# OVMS-SimpleConsole.net
KiCad netlist of a schematic drawn in EAGLE
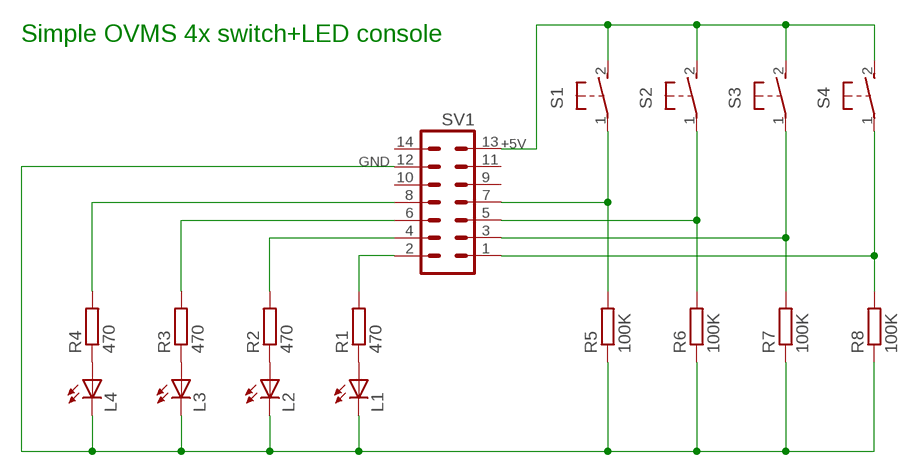
[diagram p0: schematic, sheet 1]

(export (version "E")
  (design (tool "Eeschema 10.0.6"))
  (components
    (comp (ref "L1")
      (value "LED5MM")
      (footprint "eagle-import:LED5MM")
      (libsource (lib "eagle-import") (part "LED5MM"))
    )
    (comp (ref "L2")
      (value "LED5MM")
      (footprint "eagle-import:LED5MM")
      (libsource (lib "eagle-import") (part "LED5MM"))
    )
    (comp (ref "L3")
      (value "LED5MM")
      (footprint "eagle-import:LED5MM")
      (libsource (lib "eagle-import") (part "LED5MM"))
    )
    (comp (ref "L4")
      (value "LED5MM")
      (footprint "eagle-import:LED5MM")
      (libsource (lib "eagle-import") (part "LED5MM"))
    )
    (comp (ref "R1")
      (value "470")
      (footprint "eagle-import:0204_7")
      (libsource (lib "eagle-import") (part "R-EU_0204/7"))
    )
    (comp (ref "R2")
      (value "470")
      (footprint "eagle-import:0204_7")
      (libsource (lib "eagle-import") (part "R-EU_0204/7"))
    )
    (comp (ref "R3")
      (value "470")
      (footprint "eagle-import:0204_7")
      (libsource (lib "eagle-import") (part "R-EU_0204/7"))
    )
    (comp (ref "R4")
      (value "470")
      (footprint "eagle-import:0204_7")
      (libsource (lib "eagle-import") (part "R-EU_0204/7"))
    )
    (comp (ref "R5")
      (value "100K")
      (footprint "eagle-import:0204_7")
      (libsource (lib "eagle-import") (part "R-EU_0204/7"))
    )
    (comp (ref "R6")
      (value "100K")
      (footprint "eagle-import:0204_7")
      (libsource (lib "eagle-import") (part "R-EU_0204/7"))
    )
    (comp (ref "R7")
      (value "100K")
      (footprint "eagle-import:0204_7")
      (libsource (lib "eagle-import") (part "R-EU_0204/7"))
    )
    (comp (ref "R8")
      (value "100K")
      (footprint "eagle-import:0204_7")
      (libsource (lib "eagle-import") (part "R-EU_0204/7"))
    )
    (comp (ref "S1")
      (value "31-XX")
      (footprint "eagle-import:B3F-31XX")
      (fields (field (name "MPN") "B3F-3100"))
      (libsource (lib "eagle-import") (part "31-XX"))
    )
    (comp (ref "S2")
      (value "31-XX")
      (footprint "eagle-import:B3F-31XX")
      (fields (field (name "MPN") "B3F-3100"))
      (libsource (lib "eagle-import") (part "31-XX"))
    )
    (comp (ref "S3")
      (value "31-XX")
      (footprint "eagle-import:B3F-31XX")
      (fields (field (name "MPN") "B3F-3100"))
      (libsource (lib "eagle-import") (part "31-XX"))
    )
    (comp (ref "S4")
      (value "31-XX")
      (footprint "eagle-import:B3F-31XX")
      (fields (field (name "MPN") "B3F-3100"))
      (libsource (lib "eagle-import") (part "31-XX"))
    )
    (comp (ref "SV1")
      (value "14P")
      (footprint "eagle-import:14P")
      (libsource (lib "eagle-import") (part "14P"))
    )
  )
  (nets
    (net (code "1") (name "/+5V") (class "Default")
      (node (ref "S1") (pin "2") (pinfunction "S_2") (pintype "passive"))
      (node (ref "S2") (pin "2") (pinfunction "S_2") (pintype "passive"))
      (node (ref "S3") (pin "2") (pinfunction "S_2") (pintype "passive"))
      (node (ref "S4") (pin "2") (pinfunction "S_2") (pintype "passive"))
      (node (ref "SV1") (pin "13") (pinfunction "13_13") (pintype "passive"))
    )
    (net (code "2") (name "/GND") (class "Default")
      (node (ref "L1") (pin "K") (pinfunction "C_K") (pintype "passive"))
      (node (ref "L2") (pin "K") (pinfunction "C_K") (pintype "passive"))
      (node (ref "L3") (pin "K") (pinfunction "C_K") (pintype "passive"))
      (node (ref "L4") (pin "K") (pinfunction "C_K") (pintype "passive"))
      (node (ref "R5") (pin "1") (pinfunction "1_1") (pintype "passive"))
      (node (ref "R6") (pin "1") (pinfunction "1_1") (pintype "passive"))
      (node (ref "R7") (pin "1") (pinfunction "1_1") (pintype "passive"))
      (node (ref "R8") (pin "1") (pinfunction "1_1") (pintype "passive"))
      (node (ref "SV1") (pin "12") (pinfunction "12_12") (pintype "passive"))
    )
    (net (code "3") (name "Net-(L1-PadA)") (class "Default")
      (node (ref "L1") (pin "A") (pinfunction "A_A") (pintype "passive"))
      (node (ref "R1") (pin "1") (pinfunction "1_1") (pintype "passive"))
    )
    (net (code "4") (name "Net-(L2-PadA)") (class "Default")
      (node (ref "L2") (pin "A") (pinfunction "A_A") (pintype "passive"))
      (node (ref "R2") (pin "1") (pinfunction "1_1") (pintype "passive"))
    )
    (net (code "5") (name "Net-(L3-PadA)") (class "Default")
      (node (ref "L3") (pin "A") (pinfunction "A_A") (pintype "passive"))
      (node (ref "R3") (pin "1") (pinfunction "1_1") (pintype "passive"))
    )
    (net (code "6") (name "Net-(L4-PadA)") (class "Default")
      (node (ref "L4") (pin "A") (pinfunction "A_A") (pintype "passive"))
      (node (ref "R4") (pin "1") (pinfunction "1_1") (pintype "passive"))
    )
    (net (code "7") (name "Net-(R1-Pad2)") (class "Default")
      (node (ref "R1") (pin "2") (pinfunction "2_2") (pintype "passive"))
      (node (ref "SV1") (pin "2") (pinfunction "2_2") (pintype "passive"))
    )
    (net (code "8") (name "Net-(R2-Pad2)") (class "Default")
      (node (ref "R2") (pin "2") (pinfunction "2_2") (pintype "passive"))
      (node (ref "SV1") (pin "4") (pinfunction "4_4") (pintype "passive"))
    )
    (net (code "9") (name "Net-(R3-Pad2)") (class "Default")
      (node (ref "R3") (pin "2") (pinfunction "2_2") (pintype "passive"))
      (node (ref "SV1") (pin "6") (pinfunction "6_6") (pintype "passive"))
    )
    (net (code "10") (name "Net-(R4-Pad2)") (class "Default")
      (node (ref "R4") (pin "2") (pinfunction "2_2") (pintype "passive"))
      (node (ref "SV1") (pin "8") (pinfunction "8_8") (pintype "passive"))
    )
    (net (code "11") (name "Net-(S1-P)") (class "Default")
      (node (ref "R5") (pin "2") (pinfunction "2_2") (pintype "passive"))
      (node (ref "S1") (pin "1") (pinfunction "P_1") (pintype "passive"))
      (node (ref "SV1") (pin "7") (pinfunction "7_7") (pintype "passive"))
    )
    (net (code "12") (name "Net-(S2-P)") (class "Default")
      (node (ref "R6") (pin "2") (pinfunction "2_2") (pintype "passive"))
      (node (ref "S2") (pin "1") (pinfunction "P_1") (pintype "passive"))
      (node (ref "SV1") (pin "5") (pinfunction "5_5") (pintype "passive"))
    )
    (net (code "13") (name "Net-(S3-P)") (class "Default")
      (node (ref "R7") (pin "2") (pinfunction "2_2") (pintype "passive"))
      (node (ref "S3") (pin "1") (pinfunction "P_1") (pintype "passive"))
      (node (ref "SV1") (pin "3") (pinfunction "3_3") (pintype "passive"))
    )
    (net (code "14") (name "Net-(S4-P)") (class "Default")
      (node (ref "R8") (pin "2") (pinfunction "2_2") (pintype "passive"))
      (node (ref "S4") (pin "1") (pinfunction "P_1") (pintype "passive"))
      (node (ref "SV1") (pin "1") (pinfunction "1_1") (pintype "passive"))
    )
    (net (code "15") (name "unconnected-(SV1-Pad9)") (class "Default")
      (node (ref "SV1") (pin "9") (pinfunction "9_9") (pintype "passive"))
    )
    (net (code "16") (name "unconnected-(SV1-Pad10)") (class "Default")
      (node (ref "SV1") (pin "10") (pinfunction "10_10") (pintype "passive"))
    )
    (net (code "17") (name "unconnected-(SV1-Pad11)") (class "Default")
      (node (ref "SV1") (pin "11") (pinfunction "11_11") (pintype "passive"))
    )
    (net (code "18") (name "unconnected-(SV1-Pad14)") (class "Default")
      (node (ref "SV1") (pin "14") (pinfunction "14_14") (pintype "passive"))
    )
  )
)
